# InterfacesA_SWITCH_LEDS.net
KiCad netlist of a schematic drawn in Altium Designer
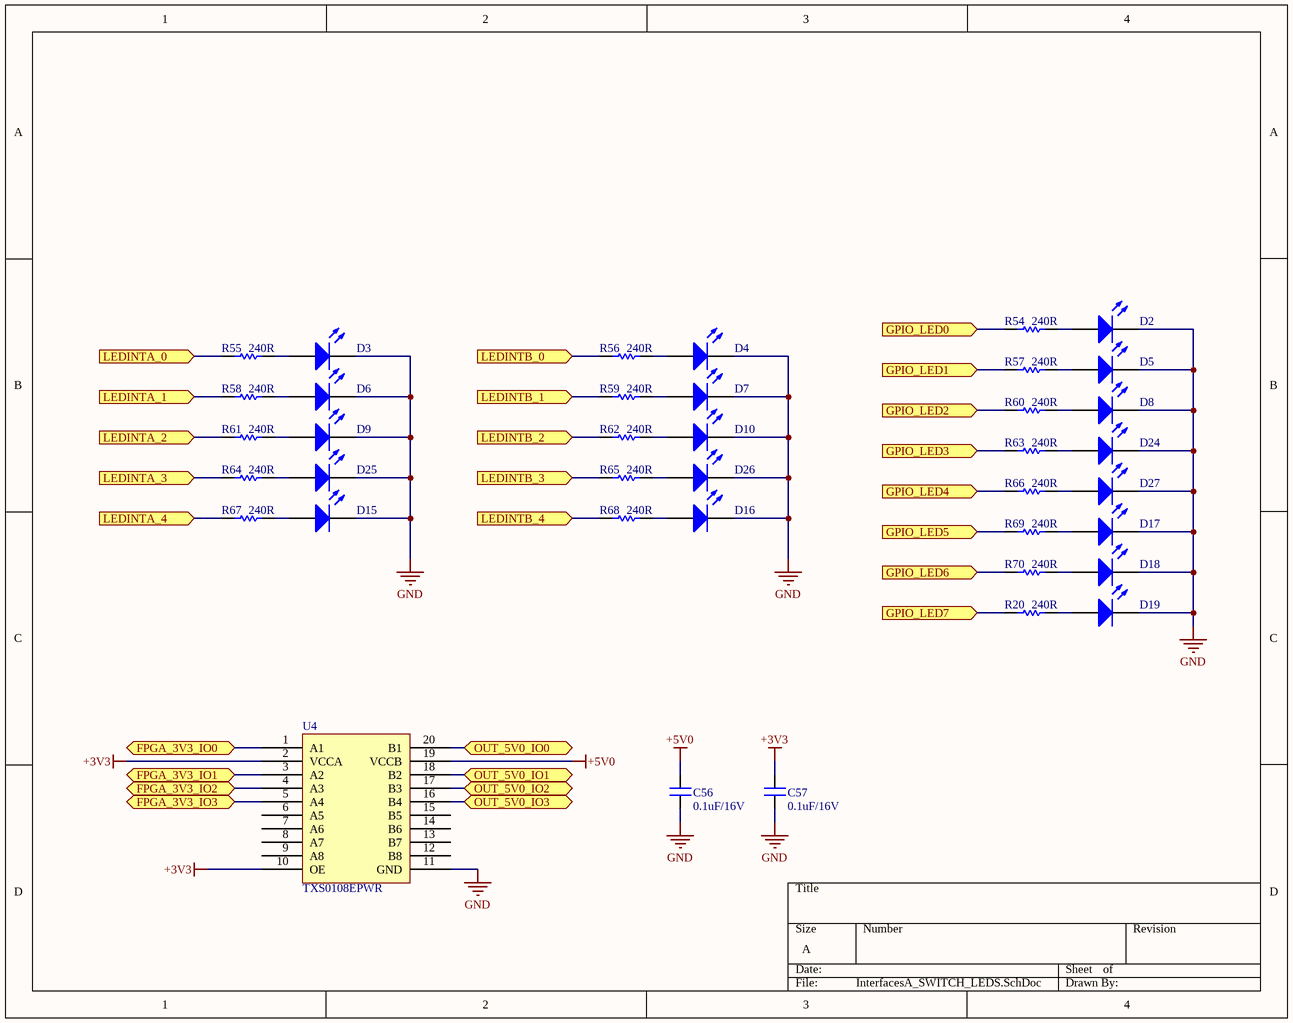
[diagram p0: InterfacesA_SWITCH_LEDS.SchDoc]

(export (version "E")
  (design (tool "Eeschema 10.0.6"))
  (components
    (comp (ref "C56")
      (value "0.1uF/16V")
      (footprint "CAP_0805")
      (fields (field (name "Comment") "CAP_0805"))
      (libsource (lib "AdapterLib") (part "CAP_0805"))
    )
    (comp (ref "C57")
      (value "0.1uF/16V")
      (footprint "CAP_0805")
      (fields (field (name "Comment") "CAP_0805"))
      (libsource (lib "AdapterLib") (part "CAP_0805"))
    )
    (comp (ref "D2")
      (value "LED_0603")
      (footprint "LED_0603")
      (libsource (lib "AdapterLib") (part "LED_0603"))
    )
    (comp (ref "D3")
      (value "LED_0603")
      (footprint "LED_0603")
      (libsource (lib "AdapterLib") (part "LED_0603"))
    )
    (comp (ref "D4")
      (value "LED_0603")
      (footprint "LED_0603")
      (libsource (lib "AdapterLib") (part "LED_0603"))
    )
    (comp (ref "D5")
      (value "LED_0603")
      (footprint "LED_0603")
      (libsource (lib "AdapterLib") (part "LED_0603"))
    )
    (comp (ref "D6")
      (value "LED_0603")
      (footprint "LED_0603")
      (libsource (lib "AdapterLib") (part "LED_0603"))
    )
    (comp (ref "D7")
      (value "LED_0603")
      (footprint "LED_0603")
      (libsource (lib "AdapterLib") (part "LED_0603"))
    )
    (comp (ref "D8")
      (value "LED_0603")
      (footprint "LED_0603")
      (libsource (lib "AdapterLib") (part "LED_0603"))
    )
    (comp (ref "D9")
      (value "LED_0603")
      (footprint "LED_0603")
      (libsource (lib "AdapterLib") (part "LED_0603"))
    )
    (comp (ref "D10")
      (value "LED_0603")
      (footprint "LED_0603")
      (libsource (lib "AdapterLib") (part "LED_0603"))
    )
    (comp (ref "D15")
      (value "LED_0603")
      (footprint "LED_0603")
      (libsource (lib "AdapterLib") (part "LED_0603"))
    )
    (comp (ref "D16")
      (value "LED_0603")
      (footprint "LED_0603")
      (libsource (lib "AdapterLib") (part "LED_0603"))
    )
    (comp (ref "D17")
      (value "LED_0603")
      (footprint "LED_0603")
      (libsource (lib "AdapterLib") (part "LED_0603"))
    )
    (comp (ref "D18")
      (value "LED_0603")
      (footprint "LED_0603")
      (libsource (lib "AdapterLib") (part "LED_0603"))
    )
    (comp (ref "D19")
      (value "LED_0603")
      (footprint "LED_0603")
      (libsource (lib "AdapterLib") (part "LED_0603"))
    )
    (comp (ref "D24")
      (value "LED_0603")
      (footprint "LED_0603")
      (libsource (lib "AdapterLib") (part "LED_0603"))
    )
    (comp (ref "D25")
      (value "LED_0603")
      (footprint "LED_0603")
      (libsource (lib "AdapterLib") (part "LED_0603"))
    )
    (comp (ref "D26")
      (value "LED_0603")
      (footprint "LED_0603")
      (libsource (lib "AdapterLib") (part "LED_0603"))
    )
    (comp (ref "D27")
      (value "LED_0603")
      (footprint "LED_0603")
      (libsource (lib "AdapterLib") (part "LED_0603"))
    )
    (comp (ref "R20")
      (value "240R")
      (footprint "RES_0805")
      (fields (field (name "Comment") "RES_0805"))
      (libsource (lib "AdapterLib") (part "RES_0805"))
    )
    (comp (ref "R54")
      (value "240R")
      (footprint "RES_0805")
      (fields (field (name "Comment") "RES_0805"))
      (libsource (lib "AdapterLib") (part "RES_0805"))
    )
    (comp (ref "R55")
      (value "240R")
      (footprint "RES_0805")
      (fields (field (name "Comment") "RES_0805"))
      (libsource (lib "AdapterLib") (part "RES_0805"))
    )
    (comp (ref "R56")
      (value "240R")
      (footprint "RES_0805")
      (fields (field (name "Comment") "RES_0805"))
      (libsource (lib "AdapterLib") (part "RES_0805"))
    )
    (comp (ref "R57")
      (value "240R")
      (footprint "RES_0805")
      (fields (field (name "Comment") "RES_0805"))
      (libsource (lib "AdapterLib") (part "RES_0805"))
    )
    (comp (ref "R58")
      (value "240R")
      (footprint "RES_0805")
      (fields (field (name "Comment") "RES_0805"))
      (libsource (lib "AdapterLib") (part "RES_0805"))
    )
    (comp (ref "R59")
      (value "240R")
      (footprint "RES_0805")
      (fields (field (name "Comment") "RES_0805"))
      (libsource (lib "AdapterLib") (part "RES_0805"))
    )
    (comp (ref "R60")
      (value "240R")
      (footprint "RES_0805")
      (fields (field (name "Comment") "RES_0805"))
      (libsource (lib "AdapterLib") (part "RES_0805"))
    )
    (comp (ref "R61")
      (value "240R")
      (footprint "RES_0805")
      (fields (field (name "Comment") "RES_0805"))
      (libsource (lib "AdapterLib") (part "RES_0805"))
    )
    (comp (ref "R62")
      (value "240R")
      (footprint "RES_0805")
      (fields (field (name "Comment") "RES_0805"))
      (libsource (lib "AdapterLib") (part "RES_0805"))
    )
    (comp (ref "R63")
      (value "240R")
      (footprint "RES_0805")
      (fields (field (name "Comment") "RES_0805"))
      (libsource (lib "AdapterLib") (part "RES_0805"))
    )
    (comp (ref "R64")
      (value "240R")
      (footprint "RES_0805")
      (fields (field (name "Comment") "RES_0805"))
      (libsource (lib "AdapterLib") (part "RES_0805"))
    )
    (comp (ref "R65")
      (value "240R")
      (footprint "RES_0805")
      (fields (field (name "Comment") "RES_0805"))
      (libsource (lib "AdapterLib") (part "RES_0805"))
    )
    (comp (ref "R66")
      (value "240R")
      (footprint "RES_0805")
      (fields (field (name "Comment") "RES_0805"))
      (libsource (lib "AdapterLib") (part "RES_0805"))
    )
    (comp (ref "R67")
      (value "240R")
      (footprint "RES_0805")
      (fields (field (name "Comment") "RES_0805"))
      (libsource (lib "AdapterLib") (part "RES_0805"))
    )
    (comp (ref "R68")
      (value "240R")
      (footprint "RES_0805")
      (fields (field (name "Comment") "RES_0805"))
      (libsource (lib "AdapterLib") (part "RES_0805"))
    )
    (comp (ref "R69")
      (value "240R")
      (footprint "RES_0805")
      (fields (field (name "Comment") "RES_0805"))
      (libsource (lib "AdapterLib") (part "RES_0805"))
    )
    (comp (ref "R70")
      (value "240R")
      (footprint "RES_0805")
      (fields (field (name "Comment") "RES_0805"))
      (libsource (lib "AdapterLib") (part "RES_0805"))
    )
    (comp (ref "U4")
      (value "TXS0108EPWR")
      (footprint "TXS0108EPWR")
      (libsource (lib "AdapterLib") (part "TXS0108EPWR"))
    )
  )
  (nets
    (net (code "1") (name "+3V3") (class "Default")
      (node (ref "C57") (pin "2") (pinfunction "2_2") (pintype "passive"))
      (node (ref "U4") (pin "10") (pinfunction "OE_10") (pintype "passive"))
      (node (ref "U4") (pin "2") (pinfunction "VCCA_2") (pintype "passive"))
    )
    (net (code "2") (name "+5V0") (class "Default")
      (node (ref "C56") (pin "2") (pinfunction "2_2") (pintype "passive"))
      (node (ref "U4") (pin "19") (pinfunction "VCCB_19") (pintype "passive"))
    )
    (net (code "3") (name "/FPGA_3V3_IO0") (class "Default")
      (node (ref "U4") (pin "1") (pinfunction "A1_1") (pintype "passive"))
    )
    (net (code "4") (name "/FPGA_3V3_IO1") (class "Default")
      (node (ref "U4") (pin "3") (pinfunction "A2_3") (pintype "passive"))
    )
    (net (code "5") (name "/FPGA_3V3_IO2") (class "Default")
      (node (ref "U4") (pin "4") (pinfunction "A3_4") (pintype "passive"))
    )
    (net (code "6") (name "/FPGA_3V3_IO3") (class "Default")
      (node (ref "U4") (pin "5") (pinfunction "A4_5") (pintype "passive"))
    )
    (net (code "7") (name "/GPIO_LED0") (class "Default")
      (node (ref "R54") (pin "2") (pinfunction "2_2") (pintype "passive"))
    )
    (net (code "8") (name "/GPIO_LED1") (class "Default")
      (node (ref "R57") (pin "2") (pinfunction "2_2") (pintype "passive"))
    )
    (net (code "9") (name "/GPIO_LED2") (class "Default")
      (node (ref "R60") (pin "2") (pinfunction "2_2") (pintype "passive"))
    )
    (net (code "10") (name "/GPIO_LED3") (class "Default")
      (node (ref "R63") (pin "2") (pinfunction "2_2") (pintype "passive"))
    )
    (net (code "11") (name "/GPIO_LED4") (class "Default")
      (node (ref "R66") (pin "2") (pinfunction "2_2") (pintype "passive"))
    )
    (net (code "12") (name "/GPIO_LED5") (class "Default")
      (node (ref "R69") (pin "2") (pinfunction "2_2") (pintype "passive"))
    )
    (net (code "13") (name "/GPIO_LED6") (class "Default")
      (node (ref "R70") (pin "2") (pinfunction "2_2") (pintype "passive"))
    )
    (net (code "14") (name "/GPIO_LED7") (class "Default")
      (node (ref "R20") (pin "2") (pinfunction "2_2") (pintype "passive"))
    )
    (net (code "15") (name "/LEDINTA_0") (class "Default")
      (node (ref "R55") (pin "2") (pinfunction "2_2") (pintype "passive"))
    )
    (net (code "16") (name "/LEDINTA_1") (class "Default")
      (node (ref "R58") (pin "2") (pinfunction "2_2") (pintype "passive"))
    )
    (net (code "17") (name "/LEDINTA_2") (class "Default")
      (node (ref "R61") (pin "2") (pinfunction "2_2") (pintype "passive"))
    )
    (net (code "18") (name "/LEDINTA_3") (class "Default")
      (node (ref "R64") (pin "2") (pinfunction "2_2") (pintype "passive"))
    )
    (net (code "19") (name "/LEDINTA_4") (class "Default")
      (node (ref "R67") (pin "2") (pinfunction "2_2") (pintype "passive"))
    )
    (net (code "20") (name "/LEDINTB_0") (class "Default")
      (node (ref "R56") (pin "2") (pinfunction "2_2") (pintype "passive"))
    )
    (net (code "21") (name "/LEDINTB_1") (class "Default")
      (node (ref "R59") (pin "2") (pinfunction "2_2") (pintype "passive"))
    )
    (net (code "22") (name "/LEDINTB_2") (class "Default")
      (node (ref "R62") (pin "2") (pinfunction "2_2") (pintype "passive"))
    )
    (net (code "23") (name "/LEDINTB_3") (class "Default")
      (node (ref "R65") (pin "2") (pinfunction "2_2") (pintype "passive"))
    )
    (net (code "24") (name "/LEDINTB_4") (class "Default")
      (node (ref "R68") (pin "2") (pinfunction "2_2") (pintype "passive"))
    )
    (net (code "25") (name "/OUT_5V0_IO0") (class "Default")
      (node (ref "U4") (pin "20") (pinfunction "B1_20") (pintype "passive"))
    )
    (net (code "26") (name "/OUT_5V0_IO1") (class "Default")
      (node (ref "U4") (pin "18") (pinfunction "B2_18") (pintype "passive"))
    )
    (net (code "27") (name "/OUT_5V0_IO2") (class "Default")
      (node (ref "U4") (pin "17") (pinfunction "B3_17") (pintype "passive"))
    )
    (net (code "28") (name "/OUT_5V0_IO3") (class "Default")
      (node (ref "U4") (pin "16") (pinfunction "B4_16") (pintype "passive"))
    )
    (net (code "29") (name "GND") (class "Default")
      (node (ref "C56") (pin "1") (pinfunction "1_1") (pintype "passive"))
      (node (ref "C57") (pin "1") (pinfunction "1_1") (pintype "passive"))
      (node (ref "D10") (pin "2") (pinfunction "K_2") (pintype "passive"))
      (node (ref "D15") (pin "2") (pinfunction "K_2") (pintype "passive"))
      (node (ref "D16") (pin "2") (pinfunction "K_2") (pintype "passive"))
      (node (ref "D17") (pin "2") (pinfunction "K_2") (pintype "passive"))
      (node (ref "D18") (pin "2") (pinfunction "K_2") (pintype "passive"))
      (node (ref "D19") (pin "2") (pinfunction "K_2") (pintype "passive"))
      (node (ref "D2") (pin "2") (pinfunction "K_2") (pintype "passive"))
      (node (ref "D24") (pin "2") (pinfunction "K_2") (pintype "passive"))
      (node (ref "D25") (pin "2") (pinfunction "K_2") (pintype "passive"))
      (node (ref "D26") (pin "2") (pinfunction "K_2") (pintype "passive"))
      (node (ref "D27") (pin "2") (pinfunction "K_2") (pintype "passive"))
      (node (ref "D3") (pin "2") (pinfunction "K_2") (pintype "passive"))
      (node (ref "D4") (pin "2") (pinfunction "K_2") (pintype "passive"))
      (node (ref "D5") (pin "2") (pinfunction "K_2") (pintype "passive"))
      (node (ref "D6") (pin "2") (pinfunction "K_2") (pintype "passive"))
      (node (ref "D7") (pin "2") (pinfunction "K_2") (pintype "passive"))
      (node (ref "D8") (pin "2") (pinfunction "K_2") (pintype "passive"))
      (node (ref "D9") (pin "2") (pinfunction "K_2") (pintype "passive"))
      (node (ref "U4") (pin "11") (pinfunction "GND_11") (pintype "passive"))
    )
    (net (code "30") (name "Net-(D2-A)") (class "Default")
      (node (ref "D2") (pin "1") (pinfunction "A_1") (pintype "passive"))
      (node (ref "R54") (pin "1") (pinfunction "1_1") (pintype "passive"))
    )
    (net (code "31") (name "Net-(D3-A)") (class "Default")
      (node (ref "D3") (pin "1") (pinfunction "A_1") (pintype "passive"))
      (node (ref "R55") (pin "1") (pinfunction "1_1") (pintype "passive"))
    )
    (net (code "32") (name "Net-(D4-A)") (class "Default")
      (node (ref "D4") (pin "1") (pinfunction "A_1") (pintype "passive"))
      (node (ref "R56") (pin "1") (pinfunction "1_1") (pintype "passive"))
    )
    (net (code "33") (name "Net-(D5-A)") (class "Default")
      (node (ref "D5") (pin "1") (pinfunction "A_1") (pintype "passive"))
      (node (ref "R57") (pin "1") (pinfunction "1_1") (pintype "passive"))
    )
    (net (code "34") (name "Net-(D6-A)") (class "Default")
      (node (ref "D6") (pin "1") (pinfunction "A_1") (pintype "passive"))
      (node (ref "R58") (pin "1") (pinfunction "1_1") (pintype "passive"))
    )
    (net (code "35") (name "Net-(D7-A)") (class "Default")
      (node (ref "D7") (pin "1") (pinfunction "A_1") (pintype "passive"))
      (node (ref "R59") (pin "1") (pinfunction "1_1") (pintype "passive"))
    )
    (net (code "36") (name "Net-(D8-A)") (class "Default")
      (node (ref "D8") (pin "1") (pinfunction "A_1") (pintype "passive"))
      (node (ref "R60") (pin "1") (pinfunction "1_1") (pintype "passive"))
    )
    (net (code "37") (name "Net-(D9-A)") (class "Default")
      (node (ref "D9") (pin "1") (pinfunction "A_1") (pintype "passive"))
      (node (ref "R61") (pin "1") (pinfunction "1_1") (pintype "passive"))
    )
    (net (code "38") (name "Net-(D10-A)") (class "Default")
      (node (ref "D10") (pin "1") (pinfunction "A_1") (pintype "passive"))
      (node (ref "R62") (pin "1") (pinfunction "1_1") (pintype "passive"))
    )
    (net (code "39") (name "Net-(D15-A)") (class "Default")
      (node (ref "D15") (pin "1") (pinfunction "A_1") (pintype "passive"))
      (node (ref "R67") (pin "1") (pinfunction "1_1") (pintype "passive"))
    )
    (net (code "40") (name "Net-(D16-A)") (class "Default")
      (node (ref "D16") (pin "1") (pinfunction "A_1") (pintype "passive"))
      (node (ref "R68") (pin "1") (pinfunction "1_1") (pintype "passive"))
    )
    (net (code "41") (name "Net-(D17-A)") (class "Default")
      (node (ref "D17") (pin "1") (pinfunction "A_1") (pintype "passive"))
      (node (ref "R69") (pin "1") (pinfunction "1_1") (pintype "passive"))
    )
    (net (code "42") (name "Net-(D18-A)") (class "Default")
      (node (ref "D18") (pin "1") (pinfunction "A_1") (pintype "passive"))
      (node (ref "R70") (pin "1") (pinfunction "1_1") (pintype "passive"))
    )
    (net (code "43") (name "Net-(D19-A)") (class "Default")
      (node (ref "D19") (pin "1") (pinfunction "A_1") (pintype "passive"))
      (node (ref "R20") (pin "1") (pinfunction "1_1") (pintype "passive"))
    )
    (net (code "44") (name "Net-(D24-A)") (class "Default")
      (node (ref "D24") (pin "1") (pinfunction "A_1") (pintype "passive"))
      (node (ref "R63") (pin "1") (pinfunction "1_1") (pintype "passive"))
    )
    (net (code "45") (name "Net-(D25-A)") (class "Default")
      (node (ref "D25") (pin "1") (pinfunction "A_1") (pintype "passive"))
      (node (ref "R64") (pin "1") (pinfunction "1_1") (pintype "passive"))
    )
    (net (code "46") (name "Net-(D26-A)") (class "Default")
      (node (ref "D26") (pin "1") (pinfunction "A_1") (pintype "passive"))
      (node (ref "R65") (pin "1") (pinfunction "1_1") (pintype "passive"))
    )
    (net (code "47") (name "Net-(D27-A)") (class "Default")
      (node (ref "D27") (pin "1") (pinfunction "A_1") (pintype "passive"))
      (node (ref "R66") (pin "1") (pinfunction "1_1") (pintype "passive"))
    )
    (net (code "48") (name "unconnected-(U4-A5-Pad6)") (class "Default")
      (node (ref "U4") (pin "6") (pinfunction "A5_6") (pintype "passive"))
    )
    (net (code "49") (name "unconnected-(U4-A6-Pad7)") (class "Default")
      (node (ref "U4") (pin "7") (pinfunction "A6_7") (pintype "passive"))
    )
    (net (code "50") (name "unconnected-(U4-A7-Pad8)") (class "Default")
      (node (ref "U4") (pin "8") (pinfunction "A7_8") (pintype "passive"))
    )
    (net (code "51") (name "unconnected-(U4-A8-Pad9)") (class "Default")
      (node (ref "U4") (pin "9") (pinfunction "A8_9") (pintype "passive"))
    )
    (net (code "52") (name "unconnected-(U4-B5-Pad15)") (class "Default")
      (node (ref "U4") (pin "15") (pinfunction "B5_15") (pintype "passive"))
    )
    (net (code "53") (name "unconnected-(U4-B6-Pad14)") (class "Default")
      (node (ref "U4") (pin "14") (pinfunction "B6_14") (pintype "passive"))
    )
    (net (code "54") (name "unconnected-(U4-B7-Pad13)") (class "Default")
      (node (ref "U4") (pin "13") (pinfunction "B7_13") (pintype "passive"))
    )
    (net (code "55") (name "unconnected-(U4-B8-Pad12)") (class "Default")
      (node (ref "U4") (pin "12") (pinfunction "B8_12") (pintype "passive"))
    )
  )
)
